# M105C.net
KiCad netlist of a schematic drawn in EAGLE
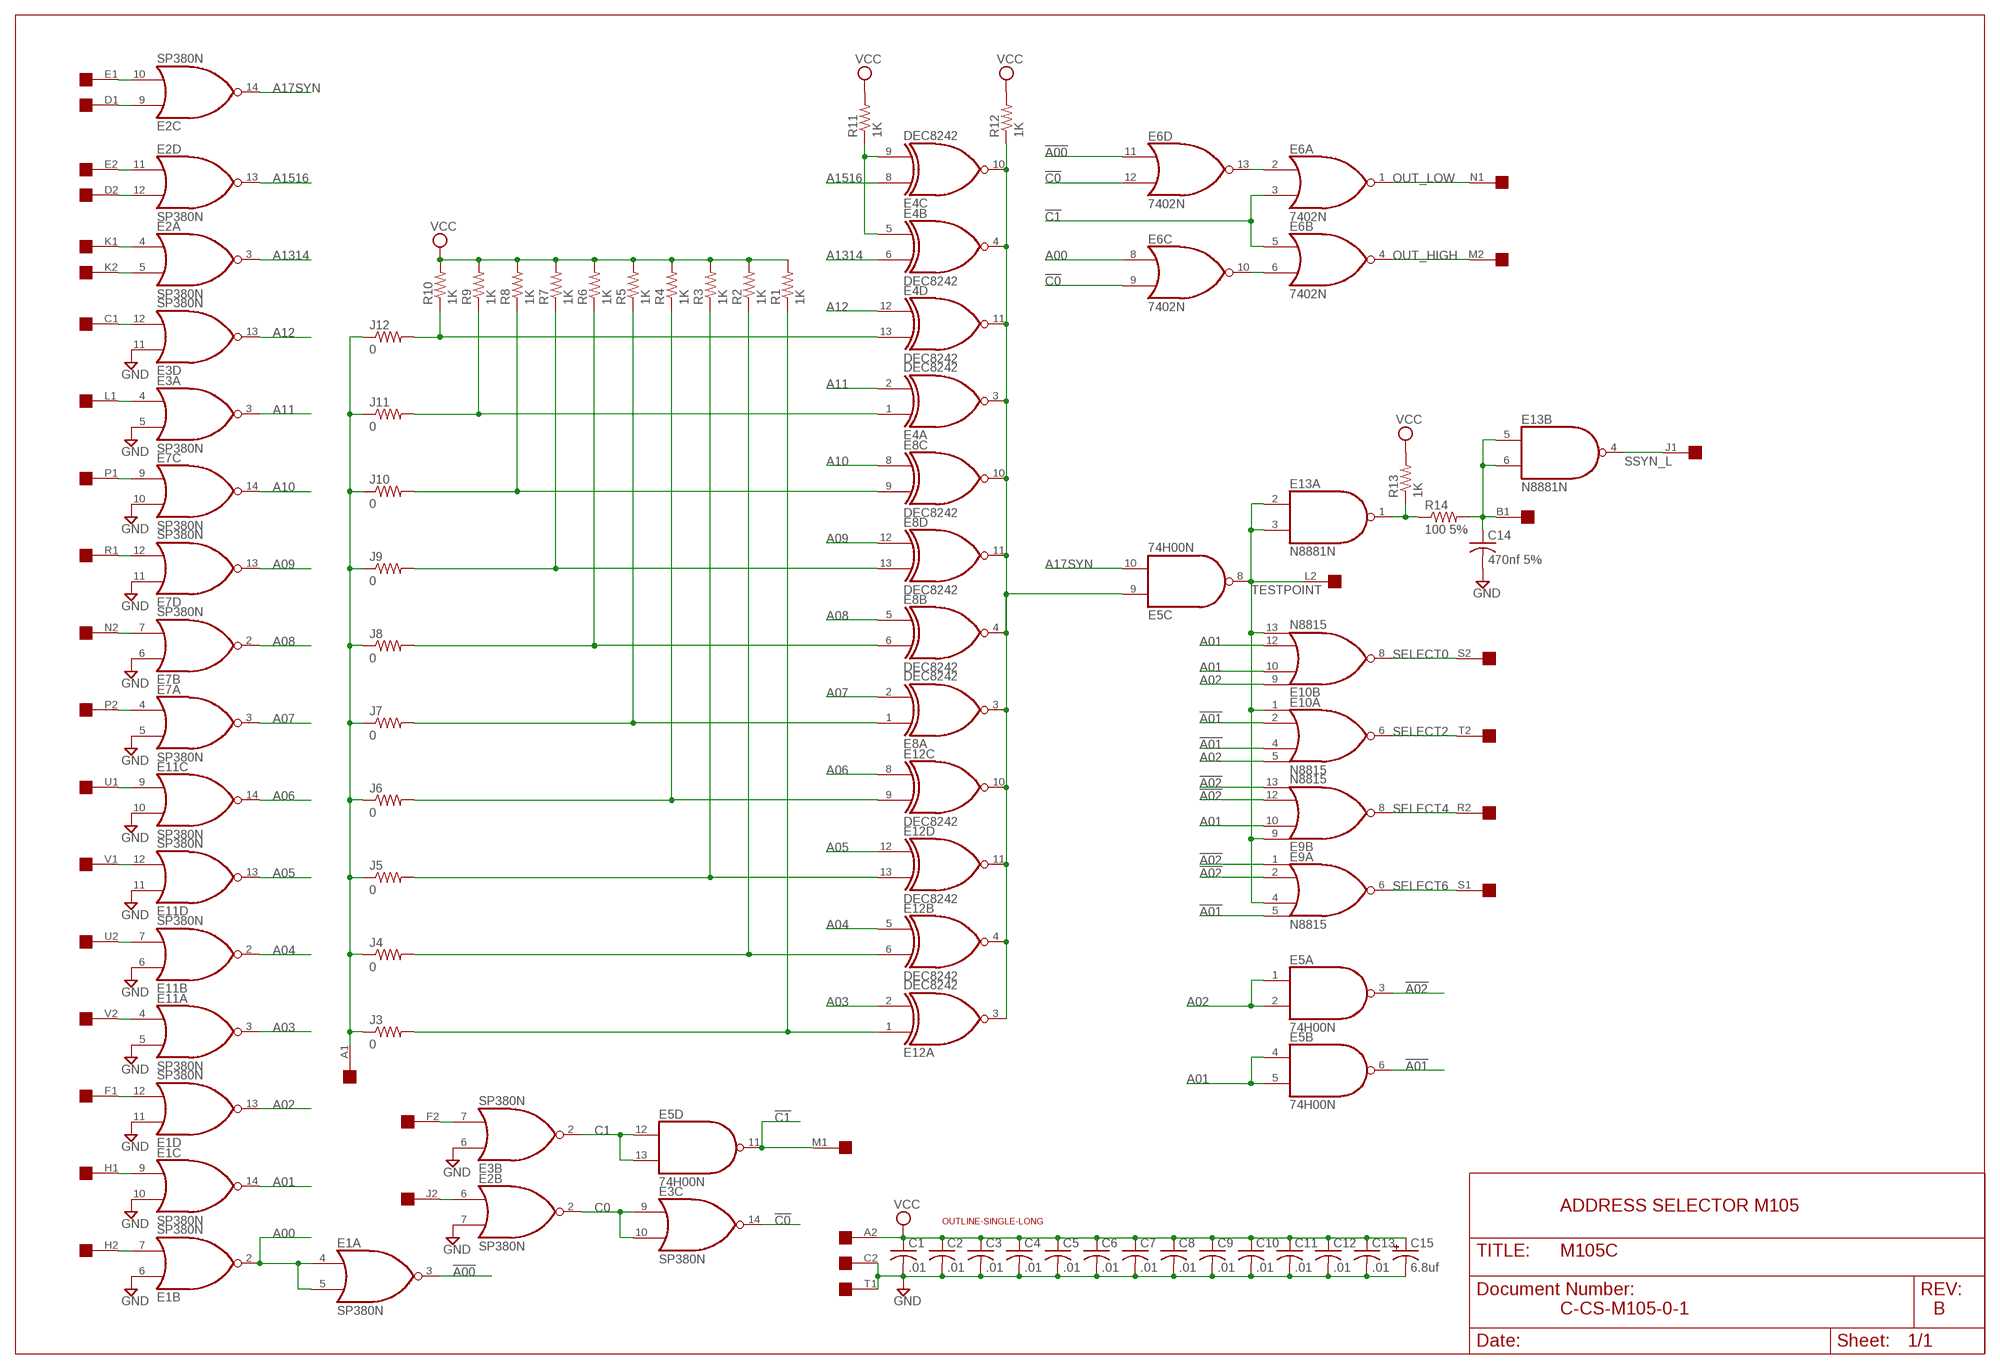
[diagram p0: schematic, sheet 1]

(export (version "E")
  (design (tool "Eeschema 10.0.6"))
  (components
    (comp (ref "C1")
      (value ".01")
      (footprint "eagle-import:C050-025X075")
      (libsource (lib "eagle-import") (part "C-US050-025X075"))
    )
    (comp (ref "C2")
      (value ".01")
      (footprint "eagle-import:C050-025X075")
      (libsource (lib "eagle-import") (part "C-US050-025X075"))
    )
    (comp (ref "C3")
      (value ".01")
      (footprint "eagle-import:C050-025X075")
      (libsource (lib "eagle-import") (part "C-US050-025X075"))
    )
    (comp (ref "C4")
      (value ".01")
      (footprint "eagle-import:C050-025X075")
      (libsource (lib "eagle-import") (part "C-US050-025X075"))
    )
    (comp (ref "C5")
      (value ".01")
      (footprint "eagle-import:C050-025X075")
      (libsource (lib "eagle-import") (part "C-US050-025X075"))
    )
    (comp (ref "C6")
      (value ".01")
      (footprint "eagle-import:C050-025X075")
      (libsource (lib "eagle-import") (part "C-US050-025X075"))
    )
    (comp (ref "C7")
      (value ".01")
      (footprint "eagle-import:C050-025X075")
      (libsource (lib "eagle-import") (part "C-US050-025X075"))
    )
    (comp (ref "C8")
      (value ".01")
      (footprint "eagle-import:C050-025X075")
      (libsource (lib "eagle-import") (part "C-US050-025X075"))
    )
    (comp (ref "C9")
      (value ".01")
      (footprint "eagle-import:C050-025X075")
      (libsource (lib "eagle-import") (part "C-US050-025X075"))
    )
    (comp (ref "C10")
      (value ".01")
      (footprint "eagle-import:C050-025X075")
      (libsource (lib "eagle-import") (part "C-US050-025X075"))
    )
    (comp (ref "C11")
      (value ".01")
      (footprint "eagle-import:C050-025X075")
      (libsource (lib "eagle-import") (part "C-US050-025X075"))
    )
    (comp (ref "C12")
      (value ".01")
      (footprint "eagle-import:C050-025X075")
      (libsource (lib "eagle-import") (part "C-US050-025X075"))
    )
    (comp (ref "C13")
      (value ".01")
      (footprint "eagle-import:C050-025X075")
      (libsource (lib "eagle-import") (part "C-US050-025X075"))
    )
    (comp (ref "C14")
      (value "470nf 5%")
      (footprint "eagle-import:C050-025X075")
      (libsource (lib "eagle-import") (part "C-US050-025X075"))
    )
    (comp (ref "C15")
      (value "6.8uf")
      (footprint "eagle-import:E15-5")
      (libsource (lib "eagle-import") (part "CPOL-USE15-5AXIAL"))
    )
    (comp (ref "E1")
      (value "SP380N")
      (footprint "eagle-import:DIL14")
      (libsource (lib "eagle-import") (part "SP380N"))
    )
    (comp (ref "E2")
      (value "SP380N")
      (footprint "eagle-import:DIL14")
      (libsource (lib "eagle-import") (part "SP380N"))
    )
    (comp (ref "E3")
      (value "SP380N")
      (footprint "eagle-import:DIL14")
      (libsource (lib "eagle-import") (part "SP380N"))
    )
    (comp (ref "E4")
      (value "DEC8242")
      (footprint "eagle-import:DIL14")
      (libsource (lib "eagle-import") (part "74266NLS"))
    )
    (comp (ref "E5")
      (value "74H00N")
      (footprint "eagle-import:DIL14")
      (libsource (lib "eagle-import") (part "7400NS"))
    )
    (comp (ref "E6")
      (value "7402N")
      (footprint "eagle-import:DIL14")
      (libsource (lib "eagle-import") (part "7402N"))
    )
    (comp (ref "E7")
      (value "SP380N")
      (footprint "eagle-import:DIL14")
      (libsource (lib "eagle-import") (part "SP380N"))
    )
    (comp (ref "E8")
      (value "DEC8242")
      (footprint "eagle-import:DIL14")
      (libsource (lib "eagle-import") (part "74266NLS"))
    )
    (comp (ref "E9")
      (value "N8815")
      (footprint "eagle-import:DIL14")
      (libsource (lib "eagle-import") (part "N8815"))
    )
    (comp (ref "E10")
      (value "N8815")
      (footprint "eagle-import:DIL14")
      (libsource (lib "eagle-import") (part "N8815"))
    )
    (comp (ref "E11")
      (value "SP380N")
      (footprint "eagle-import:DIL14")
      (libsource (lib "eagle-import") (part "SP380N"))
    )
    (comp (ref "E12")
      (value "DEC8242")
      (footprint "eagle-import:DIL14")
      (libsource (lib "eagle-import") (part "74266NLS"))
    )
    (comp (ref "E13")
      (value "N8881N")
      (footprint "eagle-import:DIL14")
      (libsource (lib "eagle-import") (part "N8881N"))
    )
    (comp (ref "J3")
      (value "0")
      (footprint "eagle-import:0207_10")
      (libsource (lib "eagle-import") (part "R-US_0207/10"))
    )
    (comp (ref "J4")
      (value "0")
      (footprint "eagle-import:0207_10")
      (libsource (lib "eagle-import") (part "R-US_0207/10"))
    )
    (comp (ref "J5")
      (value "0")
      (footprint "eagle-import:0207_10")
      (libsource (lib "eagle-import") (part "R-US_0207/10"))
    )
    (comp (ref "J6")
      (value "0")
      (footprint "eagle-import:0207_10")
      (libsource (lib "eagle-import") (part "R-US_0207/10"))
    )
    (comp (ref "J7")
      (value "0")
      (footprint "eagle-import:0207_10")
      (libsource (lib "eagle-import") (part "R-US_0207/10"))
    )
    (comp (ref "J8")
      (value "0")
      (footprint "eagle-import:0207_10")
      (libsource (lib "eagle-import") (part "R-US_0207/10"))
    )
    (comp (ref "J9")
      (value "0")
      (footprint "eagle-import:0207_10")
      (libsource (lib "eagle-import") (part "R-US_0207/10"))
    )
    (comp (ref "J10")
      (value "0")
      (footprint "eagle-import:0207_10")
      (libsource (lib "eagle-import") (part "R-US_0207/10"))
    )
    (comp (ref "J11")
      (value "0")
      (footprint "eagle-import:0207_10")
      (libsource (lib "eagle-import") (part "R-US_0207/10"))
    )
    (comp (ref "J12")
      (value "0")
      (footprint "eagle-import:0207_10")
      (libsource (lib "eagle-import") (part "R-US_0207/10"))
    )
    (comp (ref "R1")
      (value "1K")
      (footprint "eagle-import:0207_10")
      (libsource (lib "eagle-import") (part "R-US_0207/10"))
    )
    (comp (ref "R2")
      (value "1K")
      (footprint "eagle-import:0207_10")
      (libsource (lib "eagle-import") (part "R-US_0207/10"))
    )
    (comp (ref "R3")
      (value "1K")
      (footprint "eagle-import:0207_10")
      (libsource (lib "eagle-import") (part "R-US_0207/10"))
    )
    (comp (ref "R4")
      (value "1K")
      (footprint "eagle-import:0207_10")
      (libsource (lib "eagle-import") (part "R-US_0207/10"))
    )
    (comp (ref "R5")
      (value "1K")
      (footprint "eagle-import:0207_10")
      (libsource (lib "eagle-import") (part "R-US_0207/10"))
    )
    (comp (ref "R6")
      (value "1K")
      (footprint "eagle-import:0207_10")
      (libsource (lib "eagle-import") (part "R-US_0207/10"))
    )
    (comp (ref "R7")
      (value "1K")
      (footprint "eagle-import:0207_10")
      (libsource (lib "eagle-import") (part "R-US_0207/10"))
    )
    (comp (ref "R8")
      (value "1K")
      (footprint "eagle-import:0207_10")
      (libsource (lib "eagle-import") (part "R-US_0207/10"))
    )
    (comp (ref "R9")
      (value "1K")
      (footprint "eagle-import:0207_10")
      (libsource (lib "eagle-import") (part "R-US_0207/10"))
    )
    (comp (ref "R10")
      (value "1K")
      (footprint "eagle-import:0207_10")
      (libsource (lib "eagle-import") (part "R-US_0207/10"))
    )
    (comp (ref "R11")
      (value "1K")
      (footprint "eagle-import:0207_10")
      (libsource (lib "eagle-import") (part "R-US_0207/10"))
    )
    (comp (ref "R12")
      (value "1K")
      (footprint "eagle-import:0207_10")
      (libsource (lib "eagle-import") (part "R-US_0207/10"))
    )
    (comp (ref "R13")
      (value "1K")
      (footprint "eagle-import:0207_10")
      (libsource (lib "eagle-import") (part "R-US_0207/10"))
    )
    (comp (ref "R14")
      (value "100 5%")
      (footprint "eagle-import:0207_10")
      (libsource (lib "eagle-import") (part "R-US_0207/10"))
    )
    (comp (ref "U$1")
      (value "SINGLE")
      (footprint "eagle-import:EDGE-CON2")
      (libsource (lib "eagle-import") (part "SINGLE"))
    )
    (comp (ref "U$2")
      (value "OUTLINE-SINGLE-LONG")
      (footprint "eagle-import:SINGLE-LONG")
      (libsource (lib "eagle-import") (part "OUTLINE-SINGLE-LONG"))
    )
  )
  (nets
    (net (code "1") (name "/A00") (class "Default")
      (node (ref "E1") (pin "2") (pinfunction "O_2") (pintype "output"))
      (node (ref "E1") (pin "4") (pinfunction "I0_4") (pintype "input"))
      (node (ref "E1") (pin "5") (pinfunction "I1_5") (pintype "input"))
      (node (ref "E6") (pin "8") (pinfunction "I0_8") (pintype "input"))
    )
    (net (code "2") (name "/A01") (class "Default")
      (node (ref "E1") (pin "14") (pinfunction "O_14") (pintype "output"))
      (node (ref "E10") (pin "10") (pinfunction "I1_10") (pintype "input"))
      (node (ref "E10") (pin "12") (pinfunction "I2_12") (pintype "input"))
      (node (ref "E5") (pin "4") (pinfunction "I0_4") (pintype "input"))
      (node (ref "E5") (pin "5") (pinfunction "I1_5") (pintype "input"))
      (node (ref "E9") (pin "10") (pinfunction "I1_10") (pintype "input"))
    )
    (net (code "3") (name "/A02") (class "Default")
      (node (ref "E1") (pin "13") (pinfunction "O_13") (pintype "output"))
      (node (ref "E10") (pin "5") (pinfunction "I3_5") (pintype "input"))
      (node (ref "E10") (pin "9") (pinfunction "I0_9") (pintype "input"))
      (node (ref "E5") (pin "1") (pinfunction "I0_1") (pintype "input"))
      (node (ref "E5") (pin "2") (pinfunction "I1_2") (pintype "input"))
    )
    (net (code "4") (name "/A03") (class "Default")
      (node (ref "E11") (pin "3") (pinfunction "O_3") (pintype "output"))
      (node (ref "E12") (pin "2") (pinfunction "I1_2") (pintype "input"))
    )
    (net (code "5") (name "/A04") (class "Default")
      (node (ref "E11") (pin "2") (pinfunction "O_2") (pintype "output"))
      (node (ref "E12") (pin "5") (pinfunction "I0_5") (pintype "input"))
    )
    (net (code "6") (name "/A05") (class "Default")
      (node (ref "E11") (pin "13") (pinfunction "O_13") (pintype "output"))
      (node (ref "E12") (pin "12") (pinfunction "I0_12") (pintype "input"))
    )
    (net (code "7") (name "/A06") (class "Default")
      (node (ref "E11") (pin "14") (pinfunction "O_14") (pintype "output"))
      (node (ref "E12") (pin "8") (pinfunction "I0_8") (pintype "input"))
    )
    (net (code "8") (name "/A07") (class "Default")
      (node (ref "E7") (pin "3") (pinfunction "O_3") (pintype "output"))
      (node (ref "E8") (pin "2") (pinfunction "I1_2") (pintype "input"))
    )
    (net (code "9") (name "/A08") (class "Default")
      (node (ref "E7") (pin "2") (pinfunction "O_2") (pintype "output"))
      (node (ref "E8") (pin "5") (pinfunction "I0_5") (pintype "input"))
    )
    (net (code "10") (name "/A09") (class "Default")
      (node (ref "E7") (pin "13") (pinfunction "O_13") (pintype "output"))
      (node (ref "E8") (pin "12") (pinfunction "I0_12") (pintype "input"))
    )
    (net (code "11") (name "/A10") (class "Default")
      (node (ref "E7") (pin "14") (pinfunction "O_14") (pintype "output"))
      (node (ref "E8") (pin "8") (pinfunction "I0_8") (pintype "input"))
    )
    (net (code "12") (name "/A11") (class "Default")
      (node (ref "E3") (pin "3") (pinfunction "O_3") (pintype "output"))
      (node (ref "E4") (pin "2") (pinfunction "I1_2") (pintype "input"))
    )
    (net (code "13") (name "/A12") (class "Default")
      (node (ref "E3") (pin "13") (pinfunction "O_13") (pintype "output"))
      (node (ref "E4") (pin "12") (pinfunction "I0_12") (pintype "input"))
    )
    (net (code "14") (name "/A17SYN") (class "Default")
      (node (ref "E2") (pin "14") (pinfunction "O_14") (pintype "output"))
      (node (ref "E5") (pin "10") (pinfunction "I1_10") (pintype "input"))
    )
    (net (code "15") (name "/A1314") (class "Default")
      (node (ref "E2") (pin "3") (pinfunction "O_3") (pintype "output"))
      (node (ref "E4") (pin "6") (pinfunction "I1_6") (pintype "input"))
    )
    (net (code "16") (name "/A1516") (class "Default")
      (node (ref "E2") (pin "13") (pinfunction "O_13") (pintype "output"))
      (node (ref "E4") (pin "8") (pinfunction "I0_8") (pintype "input"))
    )
    (net (code "17") (name "/C0") (class "Default")
      (node (ref "E2") (pin "2") (pinfunction "O_2") (pintype "output"))
      (node (ref "E3") (pin "10") (pinfunction "I1_10") (pintype "input"))
      (node (ref "E3") (pin "9") (pinfunction "I0_9") (pintype "input"))
    )
    (net (code "18") (name "/C1") (class "Default")
      (node (ref "E3") (pin "2") (pinfunction "O_2") (pintype "output"))
      (node (ref "E5") (pin "12") (pinfunction "I0_12") (pintype "input"))
      (node (ref "E5") (pin "13") (pinfunction "I1_13") (pintype "input"))
    )
    (net (code "19") (name "/OUT_HIGH") (class "Default")
      (node (ref "E6") (pin "4") (pinfunction "O_4") (pintype "output"))
      (node (ref "U$1") (pin "M2") (pinfunction "1_M2") (pintype "bidirectional"))
    )
    (net (code "20") (name "/OUT_LOW") (class "Default")
      (node (ref "E6") (pin "1") (pinfunction "O_1") (pintype "output"))
      (node (ref "U$1") (pin "N1") (pinfunction "1_N1") (pintype "bidirectional"))
    )
    (net (code "21") (name "/SELECT0") (class "Default")
      (node (ref "E10") (pin "8") (pinfunction "O_8") (pintype "output"))
      (node (ref "U$1") (pin "S2") (pinfunction "1_S2") (pintype "bidirectional"))
    )
    (net (code "22") (name "/SELECT2") (class "Default")
      (node (ref "E10") (pin "6") (pinfunction "O_6") (pintype "output"))
      (node (ref "U$1") (pin "T2") (pinfunction "1_T2") (pintype "bidirectional"))
    )
    (net (code "23") (name "/SELECT4") (class "Default")
      (node (ref "E9") (pin "8") (pinfunction "O_8") (pintype "output"))
      (node (ref "U$1") (pin "R2") (pinfunction "1_R2") (pintype "bidirectional"))
    )
    (net (code "24") (name "/SELECT6") (class "Default")
      (node (ref "E9") (pin "6") (pinfunction "O_6") (pintype "output"))
      (node (ref "U$1") (pin "S1") (pinfunction "1_S1") (pintype "bidirectional"))
    )
    (net (code "25") (name "/SSYN_L") (class "Default")
      (node (ref "E13") (pin "4") (pinfunction "O_4") (pintype "open_collector"))
      (node (ref "U$1") (pin "J1") (pinfunction "1_J1") (pintype "bidirectional"))
    )
    (net (code "26") (name "/TESTPOINT") (class "Default")
      (node (ref "E10") (pin "1") (pinfunction "I0_1") (pintype "input"))
      (node (ref "E10") (pin "13") (pinfunction "I3_13") (pintype "input"))
      (node (ref "E13") (pin "2") (pinfunction "I0_2") (pintype "input"))
      (node (ref "E13") (pin "3") (pinfunction "I1_3") (pintype "input"))
      (node (ref "E5") (pin "8") (pinfunction "O_8") (pintype "output"))
      (node (ref "E9") (pin "4") (pinfunction "I2_4") (pintype "input"))
      (node (ref "E9") (pin "9") (pinfunction "I0_9") (pintype "input"))
      (node (ref "U$1") (pin "L2") (pinfunction "1_L2") (pintype "bidirectional"))
    )
    (net (code "27") (name "/~{A00}") (class "Default")
      (node (ref "E1") (pin "3") (pinfunction "O_3") (pintype "output"))
      (node (ref "E6") (pin "11") (pinfunction "I0_11") (pintype "input"))
    )
    (net (code "28") (name "/~{A01}") (class "Default")
      (node (ref "E10") (pin "2") (pinfunction "I1_2") (pintype "input"))
      (node (ref "E10") (pin "4") (pinfunction "I2_4") (pintype "input"))
      (node (ref "E5") (pin "6") (pinfunction "O_6") (pintype "output"))
      (node (ref "E9") (pin "5") (pinfunction "I3_5") (pintype "input"))
    )
    (net (code "29") (name "/~{A02}") (class "Default")
      (node (ref "E5") (pin "3") (pinfunction "O_3") (pintype "output"))
      (node (ref "E9") (pin "1") (pinfunction "I0_1") (pintype "input"))
      (node (ref "E9") (pin "12") (pinfunction "I2_12") (pintype "input"))
      (node (ref "E9") (pin "13") (pinfunction "I3_13") (pintype "input"))
      (node (ref "E9") (pin "2") (pinfunction "I1_2") (pintype "input"))
    )
    (net (code "30") (name "/~{C0}") (class "Default")
      (node (ref "E3") (pin "14") (pinfunction "O_14") (pintype "output"))
      (node (ref "E6") (pin "12") (pinfunction "I1_12") (pintype "input"))
      (node (ref "E6") (pin "9") (pinfunction "I1_9") (pintype "input"))
    )
    (net (code "31") (name "/~{C1}") (class "Default")
      (node (ref "E5") (pin "11") (pinfunction "O_11") (pintype "output"))
      (node (ref "E6") (pin "3") (pinfunction "I1_3") (pintype "input"))
      (node (ref "E6") (pin "5") (pinfunction "I0_5") (pintype "input"))
      (node (ref "U$1") (pin "M1") (pinfunction "1_M1") (pintype "bidirectional"))
    )
    (net (code "32") (name "GND") (class "Default")
      (node (ref "C1") (pin "2") (pinfunction "2_2") (pintype "passive"))
      (node (ref "C10") (pin "2") (pinfunction "2_2") (pintype "passive"))
      (node (ref "C11") (pin "2") (pinfunction "2_2") (pintype "passive"))
      (node (ref "C12") (pin "2") (pinfunction "2_2") (pintype "passive"))
      (node (ref "C13") (pin "2") (pinfunction "2_2") (pintype "passive"))
      (node (ref "C14") (pin "2") (pinfunction "2_2") (pintype "passive"))
      (node (ref "C15") (pin "-") (pinfunction "-_-") (pintype "passive"))
      (node (ref "C2") (pin "2") (pinfunction "2_2") (pintype "passive"))
      (node (ref "C3") (pin "2") (pinfunction "2_2") (pintype "passive"))
      (node (ref "C4") (pin "2") (pinfunction "2_2") (pintype "passive"))
      (node (ref "C5") (pin "2") (pinfunction "2_2") (pintype "passive"))
      (node (ref "C6") (pin "2") (pinfunction "2_2") (pintype "passive"))
      (node (ref "C7") (pin "2") (pinfunction "2_2") (pintype "passive"))
      (node (ref "C8") (pin "2") (pinfunction "2_2") (pintype "passive"))
      (node (ref "C9") (pin "2") (pinfunction "2_2") (pintype "passive"))
      (node (ref "E1") (pin "10") (pinfunction "I1_10") (pintype "input"))
      (node (ref "E1") (pin "11") (pinfunction "I0_11") (pintype "input"))
      (node (ref "E1") (pin "6") (pinfunction "I0_6") (pintype "input"))
      (node (ref "E11") (pin "10") (pinfunction "I1_10") (pintype "input"))
      (node (ref "E11") (pin "11") (pinfunction "I0_11") (pintype "input"))
      (node (ref "E11") (pin "5") (pinfunction "I1_5") (pintype "input"))
      (node (ref "E11") (pin "6") (pinfunction "I0_6") (pintype "input"))
      (node (ref "E2") (pin "7") (pinfunction "I1_7") (pintype "input"))
      (node (ref "E3") (pin "11") (pinfunction "I0_11") (pintype "input"))
      (node (ref "E3") (pin "5") (pinfunction "I1_5") (pintype "input"))
      (node (ref "E3") (pin "6") (pinfunction "I0_6") (pintype "input"))
      (node (ref "E7") (pin "10") (pinfunction "I1_10") (pintype "input"))
      (node (ref "E7") (pin "11") (pinfunction "I0_11") (pintype "input"))
      (node (ref "E7") (pin "5") (pinfunction "I1_5") (pintype "input"))
      (node (ref "E7") (pin "6") (pinfunction "I0_6") (pintype "input"))
      (node (ref "U$1") (pin "C2") (pinfunction "1_C2") (pintype "bidirectional"))
      (node (ref "U$1") (pin "T1") (pinfunction "1_T1") (pintype "bidirectional"))
    )
    (net (code "33") (name "Net-(E1B-I1)") (class "Default")
      (node (ref "E1") (pin "7") (pinfunction "I1_7") (pintype "input"))
      (node (ref "U$1") (pin "H2") (pinfunction "1_H2") (pintype "bidirectional"))
    )
    (net (code "34") (name "Net-(E1C-I0)") (class "Default")
      (node (ref "E1") (pin "9") (pinfunction "I0_9") (pintype "input"))
      (node (ref "U$1") (pin "H1") (pinfunction "1_H1") (pintype "bidirectional"))
    )
    (net (code "35") (name "Net-(E1D-I1)") (class "Default")
      (node (ref "E1") (pin "12") (pinfunction "I1_12") (pintype "input"))
      (node (ref "U$1") (pin "F1") (pinfunction "1_F1") (pintype "bidirectional"))
    )
    (net (code "36") (name "Net-(E2A-I0)") (class "Default")
      (node (ref "E2") (pin "4") (pinfunction "I0_4") (pintype "input"))
      (node (ref "U$1") (pin "K1") (pinfunction "1_K1") (pintype "bidirectional"))
    )
    (net (code "37") (name "Net-(E2A-I1)") (class "Default")
      (node (ref "E2") (pin "5") (pinfunction "I1_5") (pintype "input"))
      (node (ref "U$1") (pin "K2") (pinfunction "1_K2") (pintype "bidirectional"))
    )
    (net (code "38") (name "Net-(E2B-I0)") (class "Default")
      (node (ref "E2") (pin "6") (pinfunction "I0_6") (pintype "input"))
      (node (ref "U$1") (pin "J2") (pinfunction "1_J2") (pintype "bidirectional"))
    )
    (net (code "39") (name "Net-(E2C-I0)") (class "Default")
      (node (ref "E2") (pin "9") (pinfunction "I0_9") (pintype "input"))
      (node (ref "U$1") (pin "D1") (pinfunction "1_D1") (pintype "bidirectional"))
    )
    (net (code "40") (name "Net-(E2C-I1)") (class "Default")
      (node (ref "E2") (pin "10") (pinfunction "I1_10") (pintype "input"))
      (node (ref "U$1") (pin "E1") (pinfunction "1_E1") (pintype "bidirectional"))
    )
    (net (code "41") (name "Net-(E2D-I0)") (class "Default")
      (node (ref "E2") (pin "11") (pinfunction "I0_11") (pintype "input"))
      (node (ref "U$1") (pin "E2") (pinfunction "1_E2") (pintype "bidirectional"))
    )
    (net (code "42") (name "Net-(E2D-I1)") (class "Default")
      (node (ref "E2") (pin "12") (pinfunction "I1_12") (pintype "input"))
      (node (ref "U$1") (pin "D2") (pinfunction "1_D2") (pintype "bidirectional"))
    )
    (net (code "43") (name "Net-(E3A-I0)") (class "Default")
      (node (ref "E3") (pin "4") (pinfunction "I0_4") (pintype "input"))
      (node (ref "U$1") (pin "L1") (pinfunction "1_L1") (pintype "bidirectional"))
    )
    (net (code "44") (name "Net-(E3B-I1)") (class "Default")
      (node (ref "E3") (pin "7") (pinfunction "I1_7") (pintype "input"))
      (node (ref "U$1") (pin "F2") (pinfunction "1_F2") (pintype "bidirectional"))
    )
    (net (code "45") (name "Net-(E3D-I1)") (class "Default")
      (node (ref "E3") (pin "12") (pinfunction "I1_12") (pintype "input"))
      (node (ref "U$1") (pin "C1") (pinfunction "1_C1") (pintype "bidirectional"))
    )
    (net (code "46") (name "Net-(E4A-I0)") (class "Default")
      (node (ref "E4") (pin "1") (pinfunction "I0_1") (pintype "input"))
      (node (ref "J11") (pin "2") (pinfunction "2_2") (pintype "passive"))
      (node (ref "R9") (pin "1") (pinfunction "1_1") (pintype "passive"))
    )
    (net (code "47") (name "Net-(E4B-I0)") (class "Default")
      (node (ref "E4") (pin "5") (pinfunction "I0_5") (pintype "input"))
      (node (ref "E4") (pin "9") (pinfunction "I1_9") (pintype "input"))
      (node (ref "R11") (pin "1") (pinfunction "1_1") (pintype "passive"))
    )
    (net (code "48") (name "Net-(E4D-I1)") (class "Default")
      (node (ref "E4") (pin "13") (pinfunction "I1_13") (pintype "input"))
      (node (ref "J12") (pin "2") (pinfunction "2_2") (pintype "passive"))
      (node (ref "R10") (pin "1") (pinfunction "1_1") (pintype "passive"))
    )
    (net (code "49") (name "Net-(E6A-I0)") (class "Default")
      (node (ref "E6") (pin "13") (pinfunction "O_13") (pintype "output"))
      (node (ref "E6") (pin "2") (pinfunction "I0_2") (pintype "input"))
    )
    (net (code "50") (name "Net-(E6B-I1)") (class "Default")
      (node (ref "E6") (pin "10") (pinfunction "O_10") (pintype "output"))
      (node (ref "E6") (pin "6") (pinfunction "I1_6") (pintype "input"))
    )
    (net (code "51") (name "Net-(E7A-I0)") (class "Default")
      (node (ref "E7") (pin "4") (pinfunction "I0_4") (pintype "input"))
      (node (ref "U$1") (pin "P2") (pinfunction "1_P2") (pintype "bidirectional"))
    )
    (net (code "52") (name "Net-(E7B-I1)") (class "Default")
      (node (ref "E7") (pin "7") (pinfunction "I1_7") (pintype "input"))
      (node (ref "U$1") (pin "N2") (pinfunction "1_N2") (pintype "bidirectional"))
    )
    (net (code "53") (name "Net-(E7C-I0)") (class "Default")
      (node (ref "E7") (pin "9") (pinfunction "I0_9") (pintype "input"))
      (node (ref "U$1") (pin "P1") (pinfunction "1_P1") (pintype "bidirectional"))
    )
    (net (code "54") (name "Net-(E7D-I1)") (class "Default")
      (node (ref "E7") (pin "12") (pinfunction "I1_12") (pintype "input"))
      (node (ref "U$1") (pin "R1") (pinfunction "1_R1") (pintype "bidirectional"))
    )
    (net (code "55") (name "Net-(E8A-I0)") (class "Default")
      (node (ref "E8") (pin "1") (pinfunction "I0_1") (pintype "input"))
      (node (ref "J7") (pin "2") (pinfunction "2_2") (pintype "passive"))
      (node (ref "R5") (pin "1") (pinfunction "1_1") (pintype "passive"))
    )
    (net (code "56") (name "Net-(E8B-I1)") (class "Default")
      (node (ref "E8") (pin "6") (pinfunction "I1_6") (pintype "input"))
      (node (ref "J8") (pin "2") (pinfunction "2_2") (pintype "passive"))
      (node (ref "R6") (pin "1") (pinfunction "1_1") (pintype "passive"))
    )
    (net (code "57") (name "Net-(E8C-I1)") (class "Default")
      (node (ref "E8") (pin "9") (pinfunction "I1_9") (pintype "input"))
      (node (ref "J10") (pin "2") (pinfunction "2_2") (pintype "passive"))
      (node (ref "R8") (pin "1") (pinfunction "1_1") (pintype "passive"))
    )
    (net (code "58") (name "Net-(E8D-I1)") (class "Default")
      (node (ref "E8") (pin "13") (pinfunction "I1_13") (pintype "input"))
      (node (ref "J9") (pin "2") (pinfunction "2_2") (pintype "passive"))
      (node (ref "R7") (pin "1") (pinfunction "1_1") (pintype "passive"))
    )
    (net (code "59") (name "Net-(E11A-I0)") (class "Default")
      (node (ref "E11") (pin "4") (pinfunction "I0_4") (pintype "input"))
      (node (ref "U$1") (pin "V2") (pinfunction "1_V2") (pintype "bidirectional"))
    )
    (net (code "60") (name "Net-(E11B-I1)") (class "Default")
      (node (ref "E11") (pin "7") (pinfunction "I1_7") (pintype "input"))
      (node (ref "U$1") (pin "U2") (pinfunction "1_U2") (pintype "bidirectional"))
    )
    (net (code "61") (name "Net-(E11C-I0)") (class "Default")
      (node (ref "E11") (pin "9") (pinfunction "I0_9") (pintype "input"))
      (node (ref "U$1") (pin "U1") (pinfunction "1_U1") (pintype "bidirectional"))
    )
    (net (code "62") (name "Net-(E11D-I1)") (class "Default")
      (node (ref "E11") (pin "12") (pinfunction "I1_12") (pintype "input"))
      (node (ref "U$1") (pin "V1") (pinfunction "1_V1") (pintype "bidirectional"))
    )
    (net (code "63") (name "Net-(E12A-I0)") (class "Default")
      (node (ref "E12") (pin "1") (pinfunction "I0_1") (pintype "input"))
      (node (ref "J3") (pin "2") (pinfunction "2_2") (pintype "passive"))
      (node (ref "R1") (pin "1") (pinfunction "1_1") (pintype "passive"))
    )
    (net (code "64") (name "Net-(E12A-O)") (class "Default")
      (node (ref "E12") (pin "10") (pinfunction "O_10") (pintype "open_collector"))
      (node (ref "E12") (pin "11") (pinfunction "O_11") (pintype "open_collector"))
      (node (ref "E12") (pin "3") (pinfunction "O_3") (pintype "open_collector"))
      (node (ref "E12") (pin "4") (pinfunction "O_4") (pintype "open_collector"))
      (node (ref "E4") (pin "10") (pinfunction "O_10") (pintype "open_collector"))
      (node (ref "E4") (pin "11") (pinfunction "O_11") (pintype "open_collector"))
      (node (ref "E4") (pin "3") (pinfunction "O_3") (pintype "open_collector"))
      (node (ref "E4") (pin "4") (pinfunction "O_4") (pintype "open_collector"))
      (node (ref "E5") (pin "9") (pinfunction "I0_9") (pintype "input"))
      (node (ref "E8") (pin "10") (pinfunction "O_10") (pintype "open_collector"))
      (node (ref "E8") (pin "11") (pinfunction "O_11") (pintype "open_collector"))
      (node (ref "E8") (pin "3") (pinfunction "O_3") (pintype "open_collector"))
      (node (ref "E8") (pin "4") (pinfunction "O_4") (pintype "open_collector"))
      (node (ref "R12") (pin "1") (pinfunction "1_1") (pintype "passive"))
    )
    (net (code "65") (name "Net-(E12B-I1)") (class "Default")
      (node (ref "E12") (pin "6") (pinfunction "I1_6") (pintype "input"))
      (node (ref "J4") (pin "2") (pinfunction "2_2") (pintype "passive"))
      (node (ref "R2") (pin "1") (pinfunction "1_1") (pintype "passive"))
    )
    (net (code "66") (name "Net-(E12C-I1)") (class "Default")
      (node (ref "E12") (pin "9") (pinfunction "I1_9") (pintype "input"))
      (node (ref "J6") (pin "2") (pinfunction "2_2") (pintype "passive"))
      (node (ref "R4") (pin "1") (pinfunction "1_1") (pintype "passive"))
    )
    (net (code "67") (name "Net-(E12D-I1)") (class "Default")
      (node (ref "E12") (pin "13") (pinfunction "I1_13") (pintype "input"))
      (node (ref "J5") (pin "2") (pinfunction "2_2") (pintype "passive"))
      (node (ref "R3") (pin "1") (pinfunction "1_1") (pintype "passive"))
    )
    (net (code "68") (name "Net-(E13A-O)") (class "Default")
      (node (ref "E13") (pin "1") (pinfunction "O_1") (pintype "open_collector"))
      (node (ref "R13") (pin "1") (pinfunction "1_1") (pintype "passive"))
      (node (ref "R14") (pin "1") (pinfunction "1_1") (pintype "passive"))
    )
    (net (code "69") (name "Net-(E13B-I0)") (class "Default")
      (node (ref "C14") (pin "1") (pinfunction "1_1") (pintype "passive"))
      (node (ref "E13") (pin "5") (pinfunction "I0_5") (pintype "input"))
      (node (ref "E13") (pin "6") (pinfunction "I1_6") (pintype "input"))
      (node (ref "R14") (pin "2") (pinfunction "2_2") (pintype "passive"))
      (node (ref "U$1") (pin "B1") (pinfunction "1_B1") (pintype "bidirectional"))
    )
    (net (code "70") (name "Net-(U$1A-1)") (class "Default")
      (node (ref "J10") (pin "1") (pinfunction "1_1") (pintype "passive"))
      (node (ref "J11") (pin "1") (pinfunction "1_1") (pintype "passive"))
      (node (ref "J12") (pin "1") (pinfunction "1_1") (pintype "passive"))
      (node (ref "J3") (pin "1") (pinfunction "1_1") (pintype "passive"))
      (node (ref "J4") (pin "1") (pinfunction "1_1") (pintype "passive"))
      (node (ref "J5") (pin "1") (pinfunction "1_1") (pintype "passive"))
      (node (ref "J6") (pin "1") (pinfunction "1_1") (pintype "passive"))
      (node (ref "J7") (pin "1") (pinfunction "1_1") (pintype "passive"))
      (node (ref "J8") (pin "1") (pinfunction "1_1") (pintype "passive"))
      (node (ref "J9") (pin "1") (pinfunction "1_1") (pintype "passive"))
      (node (ref "U$1") (pin "A1") (pinfunction "1_A1") (pintype "bidirectional"))
    )
    (net (code "71") (name "VCC") (class "Default")
      (node (ref "C1") (pin "1") (pinfunction "1_1") (pintype "passive"))
      (node (ref "C10") (pin "1") (pinfunction "1_1") (pintype "passive"))
      (node (ref "C11") (pin "1") (pinfunction "1_1") (pintype "passive"))
      (node (ref "C12") (pin "1") (pinfunction "1_1") (pintype "passive"))
      (node (ref "C13") (pin "1") (pinfunction "1_1") (pintype "passive"))
      (node (ref "C15") (pin "+") (pinfunction "+_+") (pintype "passive"))
      (node (ref "C2") (pin "1") (pinfunction "1_1") (pintype "passive"))
      (node (ref "C3") (pin "1") (pinfunction "1_1") (pintype "passive"))
      (node (ref "C4") (pin "1") (pinfunction "1_1") (pintype "passive"))
      (node (ref "C5") (pin "1") (pinfunction "1_1") (pintype "passive"))
      (node (ref "C6") (pin "1") (pinfunction "1_1") (pintype "passive"))
      (node (ref "C7") (pin "1") (pinfunction "1_1") (pintype "passive"))
      (node (ref "C8") (pin "1") (pinfunction "1_1") (pintype "passive"))
      (node (ref "C9") (pin "1") (pinfunction "1_1") (pintype "passive"))
      (node (ref "R1") (pin "2") (pinfunction "2_2") (pintype "passive"))
      (node (ref "R10") (pin "2") (pinfunction "2_2") (pintype "passive"))
      (node (ref "R11") (pin "2") (pinfunction "2_2") (pintype "passive"))
      (node (ref "R12") (pin "2") (pinfunction "2_2") (pintype "passive"))
      (node (ref "R13") (pin "2") (pinfunction "2_2") (pintype "passive"))
      (node (ref "R2") (pin "2") (pinfunction "2_2") (pintype "passive"))
      (node (ref "R3") (pin "2") (pinfunction "2_2") (pintype "passive"))
      (node (ref "R4") (pin "2") (pinfunction "2_2") (pintype "passive"))
      (node (ref "R5") (pin "2") (pinfunction "2_2") (pintype "passive"))
      (node (ref "R6") (pin "2") (pinfunction "2_2") (pintype "passive"))
      (node (ref "R7") (pin "2") (pinfunction "2_2") (pintype "passive"))
      (node (ref "R8") (pin "2") (pinfunction "2_2") (pintype "passive"))
      (node (ref "R9") (pin "2") (pinfunction "2_2") (pintype "passive"))
      (node (ref "U$1") (pin "A2") (pinfunction "1_A2") (pintype "bidirectional"))
    )
  )
)
